# ADC_DAC.net
KiCad netlist of a schematic drawn in Altium Designer
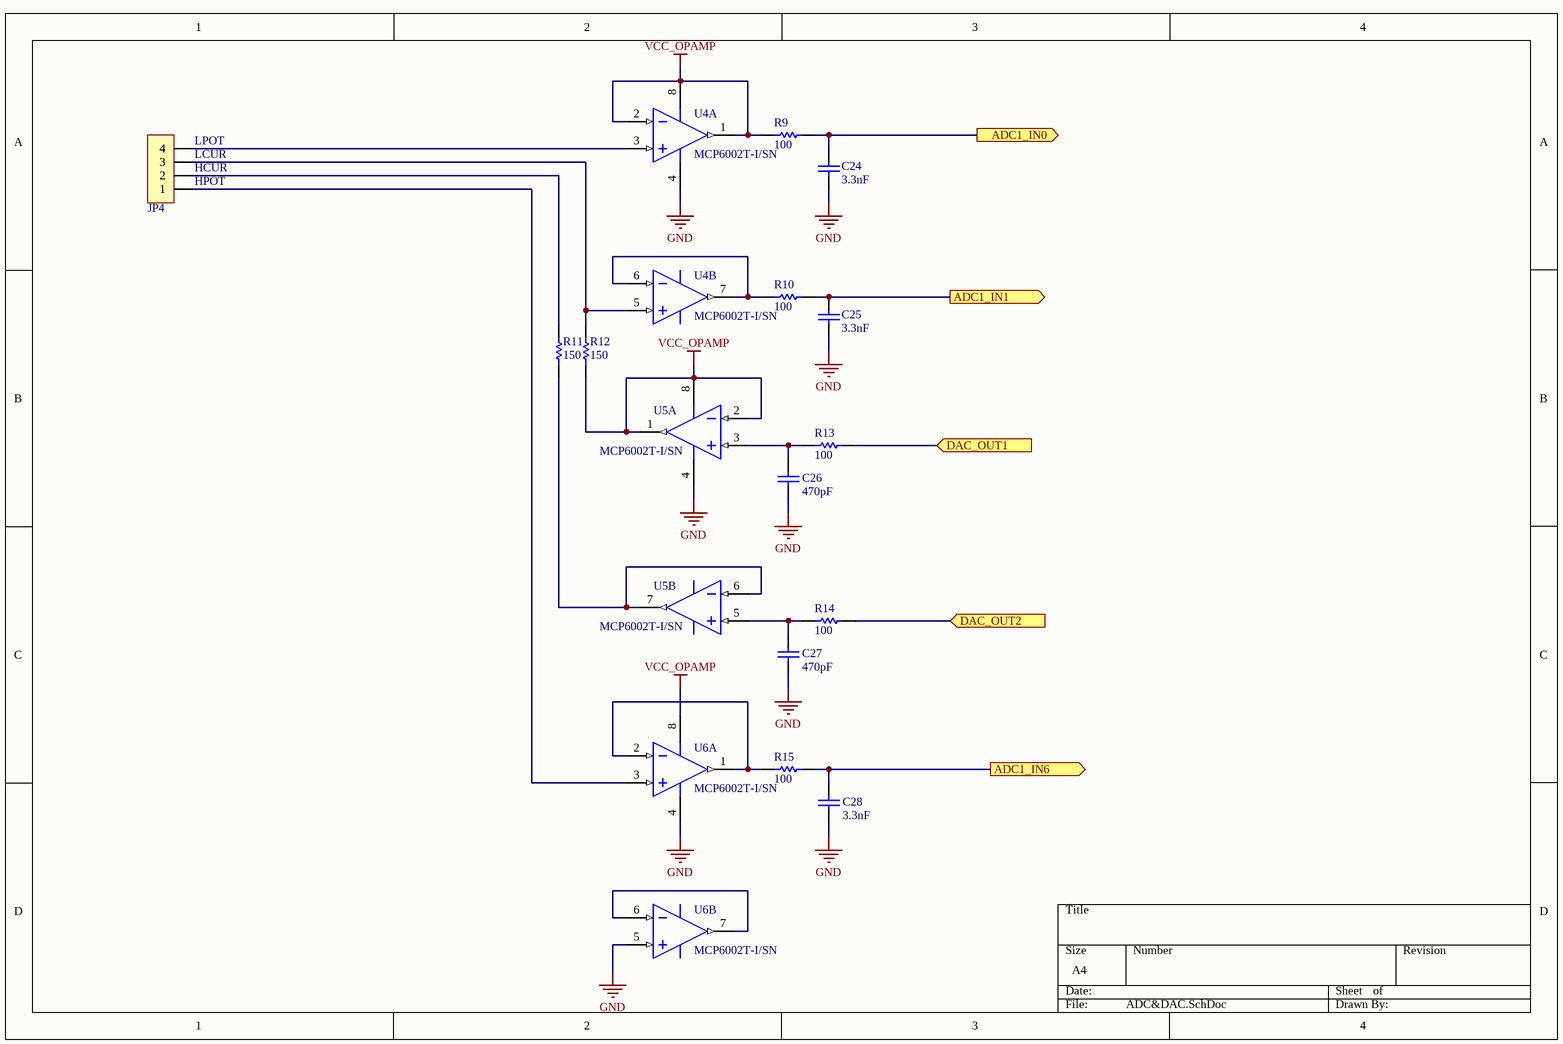
[diagram p0: ADC&DAC.SchDoc]

(export (version "E")
  (design (tool "Eeschema 10.0.6"))
  (components
    (comp (ref "C24")
      (value "3.3nF")
      (footprint "mini_rlc:new_0805")
      (description "Capacitor")
      (fields (field (name "Comment") "Cap") (field (name "PUBLISHER") "Altium Limited"))
      (libsource (lib "Miscellaneous Devices") (part "Cap"))
    )
    (comp (ref "C25")
      (value "3.3nF")
      (footprint "mini_rlc:new_0805")
      (description "Capacitor")
      (fields (field (name "Comment") "Cap") (field (name "PUBLISHER") "Altium Limited"))
      (libsource (lib "Miscellaneous Devices") (part "Cap"))
    )
    (comp (ref "C26")
      (value "470pF")
      (footprint "mini_rlc:new_0805")
      (description "Capacitor")
      (fields (field (name "Comment") "Cap") (field (name "PUBLISHER") "Altium Limited"))
      (libsource (lib "Miscellaneous Devices") (part "Cap"))
    )
    (comp (ref "C27")
      (value "470pF")
      (footprint "mini_rlc:new_0805")
      (description "Capacitor")
      (fields (field (name "Comment") "Cap") (field (name "PUBLISHER") "Altium Limited"))
      (libsource (lib "Miscellaneous Devices") (part "Cap"))
    )
    (comp (ref "C28")
      (value "3.3nF")
      (footprint "mini_rlc:new_0805")
      (description "Capacitor")
      (fields (field (name "Comment") "Cap") (field (name "PUBLISHER") "Altium Limited"))
      (libsource (lib "Miscellaneous Devices") (part "Cap"))
    )
    (comp (ref "JP4")
      (value "HDR-1X4")
      (footprint "XH2.54-WI-4P")
      (description "4P接插件")
      (fields (field (name "版权归属") "封装库来自淘宝 ID：黄晶宝石"))
      (libsource (lib "5.4 - 接插件-脚距2.54 (100mil) ") (part "Header 4"))
    )
    (comp (ref "R9")
      (value "100")
      (footprint "mini_rlc:new_0805")
      (description "Resistor")
      (fields (field (name "Comment") "Res1") (field (name "PUBLISHER") "Altium Limited"))
      (libsource (lib "Miscellaneous Devices") (part "Res1"))
    )
    (comp (ref "R10")
      (value "100")
      (footprint "mini_rlc:new_0805")
      (description "Resistor")
      (fields (field (name "Comment") "Res1") (field (name "PUBLISHER") "Altium Limited"))
      (libsource (lib "Miscellaneous Devices") (part "Res1"))
    )
    (comp (ref "R11")
      (value "150")
      (footprint "new_0805")
      (description "Resistor")
      (fields (field (name "Comment") "Res1") (field (name "PUBLISHER") "Altium Limited"))
      (libsource (lib "Miscellaneous Devices") (part "Res1"))
    )
    (comp (ref "R12")
      (value "150")
      (footprint "new_0805")
      (description "Resistor")
      (fields (field (name "Comment") "Res1") (field (name "PUBLISHER") "Altium Limited"))
      (libsource (lib "Miscellaneous Devices") (part "Res1"))
    )
    (comp (ref "R13")
      (value "100")
      (footprint "mini_rlc:new_0805")
      (description "Resistor")
      (fields (field (name "Comment") "Res1") (field (name "PUBLISHER") "Altium Limited"))
      (libsource (lib "Miscellaneous Devices") (part "Res1"))
    )
    (comp (ref "R14")
      (value "100")
      (footprint "mini_rlc:new_0805")
      (description "Resistor")
      (fields (field (name "Comment") "Res1") (field (name "PUBLISHER") "Altium Limited"))
      (libsource (lib "Miscellaneous Devices") (part "Res1"))
    )
    (comp (ref "R15")
      (value "100")
      (footprint "mini_rlc:new_0805")
      (description "Resistor")
      (fields (field (name "Comment") "Res1") (field (name "PUBLISHER") "Altium Limited"))
      (libsource (lib "Miscellaneous Devices") (part "Res1"))
    )
    (comp (ref "U4")
      (value "MCP6002T-I/SN")
      (footprint "mini_rlc:SOIC-SN8_N")
      (description "1 MHz, Low-Power Operational Amplifier, 8-Pin SOIC, Industrial Temperature, Tape and Reel")
      (fields (field (name "MANUFACTURER") "Microchip"))
      (libsource (lib "Microchip Linear") (part "MCP6002T-I/SN"))
    )
    (comp (ref "U5")
      (value "MCP6002T-I/SN")
      (footprint "mini_rlc:SOIC-SN8_N")
      (description "1 MHz, Low-Power Operational Amplifier, 8-Pin SOIC, Industrial Temperature, Tape and Reel")
      (fields (field (name "MANUFACTURER") "Microchip"))
      (libsource (lib "Microchip Linear") (part "MCP6002T-I/SN"))
    )
    (comp (ref "U6")
      (value "MCP6002T-I/SN")
      (footprint "mini_rlc:SOIC-SN8_N")
      (description "1 MHz, Low-Power Operational Amplifier, 8-Pin SOIC, Industrial Temperature, Tape and Reel")
      (fields (field (name "MANUFACTURER") "Microchip"))
      (libsource (lib "Microchip Linear") (part "MCP6002T-I/SN"))
    )
  )
  (nets
    (net (code "1") (name "/ADC1_IN0") (class "Default")
      (node (ref "C24") (pin "1") (pinfunction "1_1") (pintype "passive"))
      (node (ref "R9") (pin "2") (pinfunction "2_2") (pintype "passive"))
    )
    (net (code "2") (name "/ADC1_IN1") (class "Default")
      (node (ref "C25") (pin "1") (pinfunction "1_1") (pintype "passive"))
      (node (ref "R10") (pin "2") (pinfunction "2_2") (pintype "passive"))
    )
    (net (code "3") (name "/ADC1_IN6") (class "Default")
      (node (ref "C28") (pin "2") (pinfunction "2_2") (pintype "passive"))
      (node (ref "R15") (pin "2") (pinfunction "2_2") (pintype "passive"))
    )
    (net (code "4") (name "/DAC_OUT1") (class "Default")
      (node (ref "R13") (pin "2") (pinfunction "2_2") (pintype "passive"))
    )
    (net (code "5") (name "/DAC_OUT2") (class "Default")
      (node (ref "R14") (pin "2") (pinfunction "2_2") (pintype "passive"))
    )
    (net (code "6") (name "GND") (class "Default")
      (node (ref "C24") (pin "2") (pinfunction "2_2") (pintype "passive"))
      (node (ref "C25") (pin "2") (pinfunction "2_2") (pintype "passive"))
      (node (ref "C26") (pin "1") (pinfunction "1_1") (pintype "passive"))
      (node (ref "C27") (pin "1") (pinfunction "1_1") (pintype "passive"))
      (node (ref "C28") (pin "1") (pinfunction "1_1") (pintype "passive"))
      (node (ref "U4") (pin "4") (pinfunction "VSS_4") (pintype "power_in"))
      (node (ref "U5") (pin "4") (pinfunction "VSS_4") (pintype "power_in"))
      (node (ref "U6") (pin "4") (pinfunction "VSS_4") (pintype "power_in"))
      (node (ref "U6") (pin "5") (pinfunction "VINB+_5") (pintype "input"))
    )
    (net (code "7") (name "Net-(JP4-Pad2)") (class "Default")
      (node (ref "JP4") (pin "2") (pinfunction "2_2") (pintype "passive"))
      (node (ref "R11") (pin "2") (pinfunction "2_2") (pintype "passive"))
    )
    (net (code "8") (name "Net-(U4A-VINA+)") (class "Default")
      (node (ref "JP4") (pin "4") (pinfunction "4_4") (pintype "passive"))
      (node (ref "U4") (pin "3") (pinfunction "VINA+_3") (pintype "input"))
    )
    (net (code "9") (name "Net-(U4B-VINB+)") (class "Default")
      (node (ref "JP4") (pin "3") (pinfunction "3_3") (pintype "passive"))
      (node (ref "R12") (pin "2") (pinfunction "2_2") (pintype "passive"))
      (node (ref "U4") (pin "5") (pinfunction "VINB+_5") (pintype "input"))
    )
    (net (code "10") (name "Net-(U4B-VINB-)") (class "Default")
      (node (ref "R10") (pin "1") (pinfunction "1_1") (pintype "passive"))
      (node (ref "U4") (pin "6") (pinfunction "VINB-_6") (pintype "input"))
      (node (ref "U4") (pin "7") (pinfunction "VOUTB_7") (pintype "output"))
    )
    (net (code "11") (name "Net-(U5A-VINA+)") (class "Default")
      (node (ref "C26") (pin "2") (pinfunction "2_2") (pintype "passive"))
      (node (ref "R13") (pin "1") (pinfunction "1_1") (pintype "passive"))
      (node (ref "U5") (pin "3") (pinfunction "VINA+_3") (pintype "input"))
    )
    (net (code "12") (name "Net-(U5B-VINB+)") (class "Default")
      (node (ref "C27") (pin "2") (pinfunction "2_2") (pintype "passive"))
      (node (ref "R14") (pin "1") (pinfunction "1_1") (pintype "passive"))
      (node (ref "U5") (pin "5") (pinfunction "VINB+_5") (pintype "input"))
    )
    (net (code "13") (name "Net-(U5B-VINB-)") (class "Default")
      (node (ref "R11") (pin "1") (pinfunction "1_1") (pintype "passive"))
      (node (ref "U5") (pin "6") (pinfunction "VINB-_6") (pintype "input"))
      (node (ref "U5") (pin "7") (pinfunction "VOUTB_7") (pintype "output"))
    )
    (net (code "14") (name "Net-(U6A-VINA+)") (class "Default")
      (node (ref "JP4") (pin "1") (pinfunction "1_1") (pintype "passive"))
      (node (ref "U6") (pin "3") (pinfunction "VINA+_3") (pintype "input"))
    )
    (net (code "15") (name "Net-(U6A-VINA-)") (class "Default")
      (node (ref "R15") (pin "1") (pinfunction "1_1") (pintype "passive"))
      (node (ref "U6") (pin "1") (pinfunction "VOUTA_1") (pintype "output"))
      (node (ref "U6") (pin "2") (pinfunction "VINA-_2") (pintype "input"))
    )
    (net (code "16") (name "Net-(U6B-VINB-)") (class "Default")
      (node (ref "U6") (pin "6") (pinfunction "VINB-_6") (pintype "input"))
      (node (ref "U6") (pin "7") (pinfunction "VOUTB_7") (pintype "output"))
    )
    (net (code "17") (name "VCC_OPAMP") (class "Default")
      (node (ref "R12") (pin "1") (pinfunction "1_1") (pintype "passive"))
      (node (ref "R9") (pin "1") (pinfunction "1_1") (pintype "passive"))
      (node (ref "U4") (pin "1") (pinfunction "VOUTA_1") (pintype "output"))
      (node (ref "U4") (pin "2") (pinfunction "VINA-_2") (pintype "input"))
      (node (ref "U4") (pin "8") (pinfunction "VDD_8") (pintype "power_in"))
      (node (ref "U5") (pin "1") (pinfunction "VOUTA_1") (pintype "output"))
      (node (ref "U5") (pin "2") (pinfunction "VINA-_2") (pintype "input"))
      (node (ref "U5") (pin "8") (pinfunction "VDD_8") (pintype "power_in"))
      (node (ref "U6") (pin "8") (pinfunction "VDD_8") (pintype "power_in"))
    )
    (net (code "18") (name "unconnected-(U4B-VDD-Pad8)") (class "Default")
      (node (ref "U4") (pin "8") (pinfunction "VDD_8") (pintype "power_in"))
    )
    (net (code "19") (name "unconnected-(U4B-VSS-Pad4)") (class "Default")
      (node (ref "U4") (pin "4") (pinfunction "VSS_4") (pintype "power_in"))
    )
    (net (code "20") (name "unconnected-(U5B-VDD-Pad8)") (class "Default")
      (node (ref "U5") (pin "8") (pinfunction "VDD_8") (pintype "power_in"))
    )
    (net (code "21") (name "unconnected-(U5B-VSS-Pad4)") (class "Default")
      (node (ref "U5") (pin "4") (pinfunction "VSS_4") (pintype "power_in"))
    )
    (net (code "22") (name "unconnected-(U6B-VDD-Pad8)") (class "Default")
      (node (ref "U6") (pin "8") (pinfunction "VDD_8") (pintype "power_in"))
    )
    (net (code "23") (name "unconnected-(U6B-VSS-Pad4)") (class "Default")
      (node (ref "U6") (pin "4") (pinfunction "VSS_4") (pintype "power_in"))
    )
  )
)
